# Pure_SH.net
KiCad netlist of a schematic drawn in EAGLE
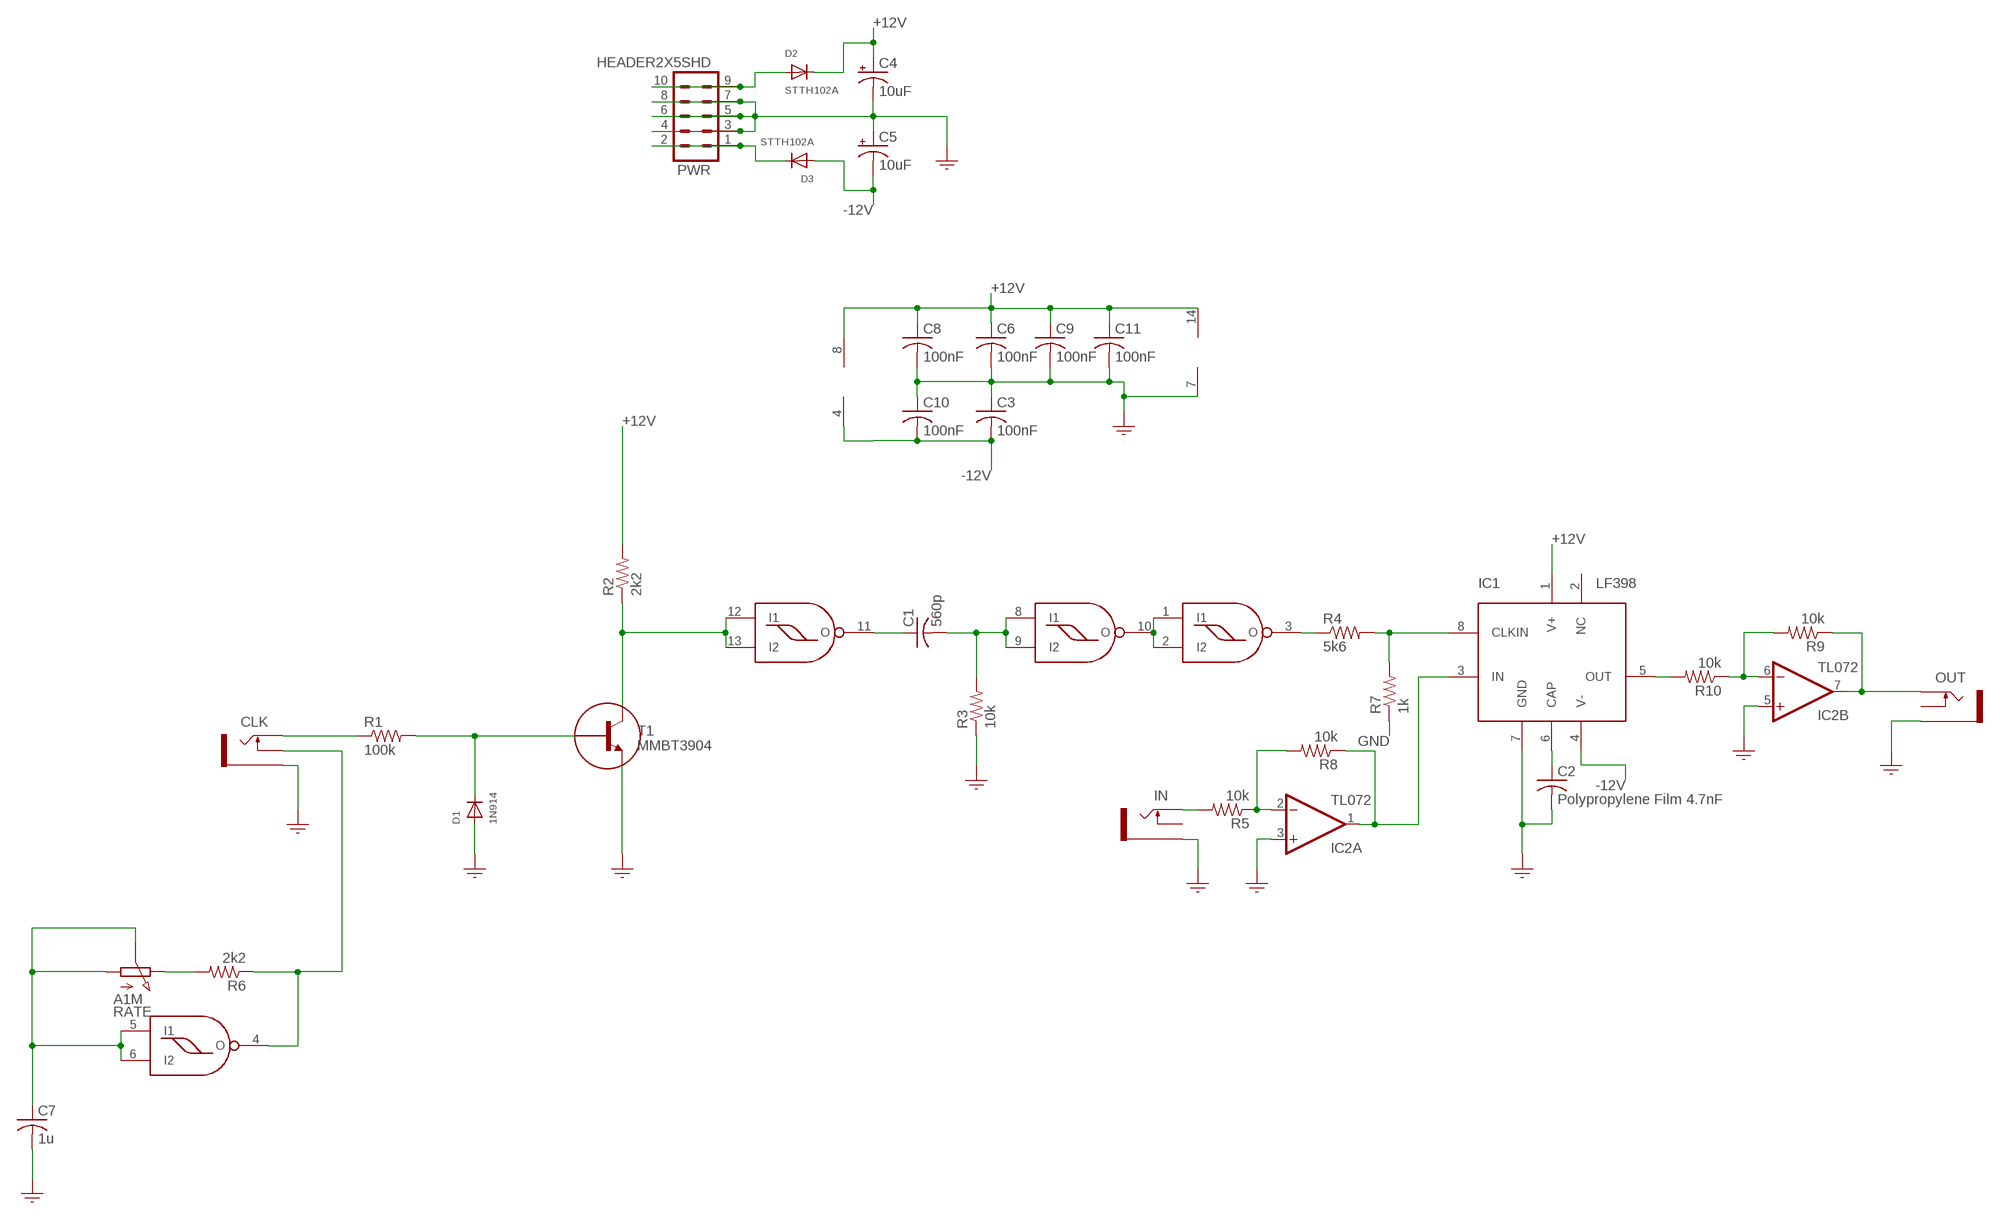
[diagram p0: schematic, sheet 1]

(export (version "E")
  (design (tool "Eeschema 10.0.6"))
  (components
    (comp (ref "C1")
      (value "560p")
      (footprint "eagle-import:C0805")
      (libsource (lib "eagle-import") (part "CAPACITOR-USC0805"))
    )
    (comp (ref "C2")
      (value "Polypropylene Film 4.7nF")
      (footprint "eagle-import:C050-045X075")
      (libsource (lib "eagle-import") (part "CAPACITOR-USC050-045X075"))
    )
    (comp (ref "C3")
      (value "100nF")
      (footprint "eagle-import:C0805")
      (libsource (lib "eagle-import") (part "CAPACITOR-USC0805"))
    )
    (comp (ref "C4")
      (value "10uF")
      (footprint "eagle-import:153CLV-0505")
      (libsource (lib "eagle-import") (part "CAPACITOR_POL-US153CLV-0505"))
    )
    (comp (ref "C5")
      (value "10uF")
      (footprint "eagle-import:153CLV-0505")
      (libsource (lib "eagle-import") (part "CAPACITOR_POL-US153CLV-0505"))
    )
    (comp (ref "C6")
      (value "100nF")
      (footprint "eagle-import:C0805")
      (libsource (lib "eagle-import") (part "CAPACITOR-USC0805"))
    )
    (comp (ref "C7")
      (value "1u")
      (footprint "eagle-import:C0805")
      (libsource (lib "eagle-import") (part "CAPACITOR-USC0805"))
    )
    (comp (ref "C8")
      (value "100nF")
      (footprint "eagle-import:C0805")
      (libsource (lib "eagle-import") (part "CAPACITOR-USC0805"))
    )
    (comp (ref "C9")
      (value "100nF")
      (footprint "eagle-import:C0805")
      (libsource (lib "eagle-import") (part "CAPACITOR-USC0805"))
    )
    (comp (ref "C10")
      (value "100nF")
      (footprint "eagle-import:C0805")
      (libsource (lib "eagle-import") (part "CAPACITOR-USC0805"))
    )
    (comp (ref "C11")
      (value "100nF")
      (footprint "eagle-import:C0805")
      (libsource (lib "eagle-import") (part "CAPACITOR-USC0805"))
    )
    (comp (ref "CLK")
      (value "PJ301M-12")
      (footprint "eagle-import:PJ301M-12")
      (libsource (lib "eagle-import") (part "SOCKET_MONO_3.5MMPJ301M-12"))
    )
    (comp (ref "D1")
      (value "1N914")
      (footprint "eagle-import:DO-41")
      (libsource (lib "eagle-import") (part "DIODEDO-41"))
    )
    (comp (ref "D2")
      (value "STTH102A")
      (footprint "eagle-import:SMADIODE")
      (libsource (lib "eagle-import") (part "DIODESMA"))
    )
    (comp (ref "D3")
      (value "STTH102A")
      (footprint "eagle-import:SMADIODE")
      (libsource (lib "eagle-import") (part "DIODESMA"))
    )
    (comp (ref "IC1")
      (value "LF398")
      (footprint "eagle-import:SOIC--8")
      (libsource (lib "eagle-import") (part "SAMPLE_HOLD_LF398"))
    )
    (comp (ref "IC2")
      (value "TL072")
      (footprint "eagle-import:SO08")
      (libsource (lib "eagle-import") (part "OPAMP_DUALD"))
    )
    (comp (ref "IC3")
      (value "cd4093")
      (footprint "eagle-import:SOIC14")
      (libsource (lib "eagle-import") (part "SCHMITT_TRIG_QUAD"))
    )
    (comp (ref "IN")
      (value "PJ301M-12")
      (footprint "eagle-import:PJ301M-12")
      (libsource (lib "eagle-import") (part "SOCKET_MONO_3.5MMPJ301M-12"))
    )
    (comp (ref "OUT")
      (value "PJ301M-12")
      (footprint "eagle-import:PJ301M-12")
      (libsource (lib "eagle-import") (part "SOCKET_MONO_3.5MMPJ301M-12"))
    )
    (comp (ref "PWR")
      (value "HEADER2X5SHD")
      (footprint "eagle-import:2X5-SHROUDED")
      (libsource (lib "eagle-import") (part "HEADER2X5SHD"))
    )
    (comp (ref "R1")
      (value "100k")
      (footprint "eagle-import:R0805")
      (libsource (lib "eagle-import") (part "RESISTOR_USR0805"))
    )
    (comp (ref "R2")
      (value "2k2")
      (footprint "eagle-import:R0805")
      (libsource (lib "eagle-import") (part "RESISTOR_USR0805"))
    )
    (comp (ref "R3")
      (value "10k")
      (footprint "eagle-import:R0805")
      (libsource (lib "eagle-import") (part "RESISTOR_USR0805"))
    )
    (comp (ref "R4")
      (value "5k6")
      (footprint "eagle-import:R0805")
      (libsource (lib "eagle-import") (part "RESISTOR_USR0805"))
    )
    (comp (ref "R5")
      (value "10k")
      (footprint "eagle-import:R0805")
      (libsource (lib "eagle-import") (part "RESISTOR_USR0805"))
    )
    (comp (ref "R6")
      (value "2k2")
      (footprint "eagle-import:R0805")
      (libsource (lib "eagle-import") (part "RESISTOR_USR0805"))
    )
    (comp (ref "R7")
      (value "1k")
      (footprint "eagle-import:R0805")
      (libsource (lib "eagle-import") (part "RESISTOR_USR0805"))
    )
    (comp (ref "R8")
      (value "10k")
      (footprint "eagle-import:R0805")
      (libsource (lib "eagle-import") (part "RESISTOR_USR0805"))
    )
    (comp (ref "R9")
      (value "10k")
      (footprint "eagle-import:R0805")
      (libsource (lib "eagle-import") (part "RESISTOR_USR0805"))
    )
    (comp (ref "R10")
      (value "10k")
      (footprint "eagle-import:R0805")
      (libsource (lib "eagle-import") (part "RESISTOR_USR0805"))
    )
    (comp (ref "RATE")
      (value "A1M")
      (footprint "eagle-import:POTENTIOMETER_9MM")
      (libsource (lib "eagle-import") (part "RESISTOR_VARIABLE9MM_POT"))
    )
    (comp (ref "T1")
      (value "MMBT3904")
      (footprint "eagle-import:SOT23")
      (libsource (lib "eagle-import") (part "TRANSISTOR_NPNSOT23"))
    )
  )
  (nets
    (net (code "1") (name "/+12V") (class "Default")
      (node (ref "C11") (pin "1") (pinfunction "1_1") (pintype "passive"))
      (node (ref "C4") (pin "+") (pinfunction "+_+") (pintype "passive"))
      (node (ref "C6") (pin "1") (pinfunction "1_1") (pintype "passive"))
      (node (ref "C8") (pin "1") (pinfunction "1_1") (pintype "passive"))
      (node (ref "C9") (pin "1") (pinfunction "1_1") (pintype "passive"))
      (node (ref "D2") (pin "C") (pinfunction "C_C") (pintype "passive"))
      (node (ref "IC1") (pin "1") (pinfunction "V+_1") (pintype "bidirectional"))
      (node (ref "IC2") (pin "8") (pinfunction "V+_8") (pintype "power_in"))
      (node (ref "IC3") (pin "14") (pinfunction "V+_14") (pintype "power_in"))
      (node (ref "R2") (pin "2") (pinfunction "2_2") (pintype "passive"))
    )
    (net (code "2") (name "/-12V") (class "Default")
      (node (ref "C10") (pin "2") (pinfunction "2_2") (pintype "passive"))
      (node (ref "C3") (pin "2") (pinfunction "2_2") (pintype "passive"))
      (node (ref "C5") (pin "-") (pinfunction "-_-") (pintype "passive"))
      (node (ref "D3") (pin "A") (pinfunction "A_A") (pintype "passive"))
      (node (ref "IC1") (pin "4") (pinfunction "V-_4") (pintype "bidirectional"))
      (node (ref "IC2") (pin "4") (pinfunction "V-_4") (pintype "power_in"))
    )
    (net (code "3") (name "GND") (class "Default")
      (node (ref "C10") (pin "1") (pinfunction "1_1") (pintype "passive"))
      (node (ref "C11") (pin "2") (pinfunction "2_2") (pintype "passive"))
      (node (ref "C2") (pin "2") (pinfunction "2_2") (pintype "passive"))
      (node (ref "C3") (pin "1") (pinfunction "1_1") (pintype "passive"))
      (node (ref "C4") (pin "-") (pinfunction "-_-") (pintype "passive"))
      (node (ref "C5") (pin "+") (pinfunction "+_+") (pintype "passive"))
      (node (ref "C6") (pin "2") (pinfunction "2_2") (pintype "passive"))
      (node (ref "C7") (pin "2") (pinfunction "2_2") (pintype "passive"))
      (node (ref "C8") (pin "2") (pinfunction "2_2") (pintype "passive"))
      (node (ref "C9") (pin "2") (pinfunction "2_2") (pintype "passive"))
      (node (ref "CLK") (pin "GND") (pinfunction "SLEEVE_GND") (pintype "passive"))
      (node (ref "D1") (pin "A") (pinfunction "A_A") (pintype "passive"))
      (node (ref "IC1") (pin "7") (pinfunction "GND_7") (pintype "bidirectional"))
      (node (ref "IC2") (pin "3") (pinfunction "+IN_3") (pintype "input"))
      (node (ref "IC2") (pin "5") (pinfunction "+IN_5") (pintype "input"))
      (node (ref "IC3") (pin "7") (pinfunction "V-_7") (pintype "power_in"))
      (node (ref "IN") (pin "GND") (pinfunction "SLEEVE_GND") (pintype "passive"))
      (node (ref "OUT") (pin "GND") (pinfunction "SLEEVE_GND") (pintype "passive"))
      (node (ref "PWR") (pin "3") (pinfunction "3_3") (pintype "passive"))
      (node (ref "PWR") (pin "4") (pinfunction "4_4") (pintype "passive"))
      (node (ref "PWR") (pin "5") (pinfunction "5_5") (pintype "passive"))
      (node (ref "PWR") (pin "6") (pinfunction "6_6") (pintype "passive"))
      (node (ref "PWR") (pin "7") (pinfunction "7_7") (pintype "passive"))
      (node (ref "PWR") (pin "8") (pinfunction "8_8") (pintype "passive"))
      (node (ref "R3") (pin "1") (pinfunction "1_1") (pintype "passive"))
      (node (ref "R7") (pin "1") (pinfunction "1_1") (pintype "passive"))
      (node (ref "T1") (pin "2") (pinfunction "E_2") (pintype "passive"))
    )
    (net (code "4") (name "Net-(CLK-PadTIP)") (class "Default")
      (node (ref "CLK") (pin "TIP") (pinfunction "TIP_TIP") (pintype "passive"))
      (node (ref "R1") (pin "1") (pinfunction "1_1") (pintype "passive"))
    )
    (net (code "5") (name "Net-(CLK-SWITCH)") (class "Default")
      (node (ref "CLK") (pin "NORM") (pinfunction "SWITCH_NORM") (pintype "passive"))
      (node (ref "IC3") (pin "4") (pinfunction "O_4") (pintype "bidirectional"))
      (node (ref "R6") (pin "1") (pinfunction "1_1") (pintype "passive"))
    )
    (net (code "6") (name "Net-(D2-PadA)") (class "Default")
      (node (ref "D2") (pin "A") (pinfunction "A_A") (pintype "passive"))
      (node (ref "PWR") (pin "10") (pinfunction "10_10") (pintype "passive"))
      (node (ref "PWR") (pin "9") (pinfunction "9_9") (pintype "passive"))
    )
    (net (code "7") (name "Net-(D3-PadC)") (class "Default")
      (node (ref "D3") (pin "C") (pinfunction "C_C") (pintype "passive"))
      (node (ref "PWR") (pin "1") (pinfunction "1_1") (pintype "passive"))
      (node (ref "PWR") (pin "2") (pinfunction "2_2") (pintype "passive"))
    )
    (net (code "8") (name "Net-(IC1-CAP)") (class "Default")
      (node (ref "C2") (pin "1") (pinfunction "1_1") (pintype "passive"))
      (node (ref "IC1") (pin "6") (pinfunction "CAP_6") (pintype "bidirectional"))
    )
    (net (code "9") (name "Net-(IC1-CLKIN)") (class "Default")
      (node (ref "IC1") (pin "8") (pinfunction "CLKIN_8") (pintype "bidirectional"))
      (node (ref "R4") (pin "2") (pinfunction "2_2") (pintype "passive"))
      (node (ref "R7") (pin "2") (pinfunction "2_2") (pintype "passive"))
    )
    (net (code "10") (name "Net-(IC1-IN)") (class "Default")
      (node (ref "IC1") (pin "3") (pinfunction "IN_3") (pintype "bidirectional"))
      (node (ref "IC2") (pin "1") (pinfunction "OUT_1") (pintype "output"))
      (node (ref "R8") (pin "1") (pinfunction "1_1") (pintype "passive"))
    )
    (net (code "11") (name "Net-(IC1-OUT)") (class "Default")
      (node (ref "IC1") (pin "5") (pinfunction "OUT_5") (pintype "bidirectional"))
      (node (ref "R10") (pin "2") (pinfunction "2_2") (pintype "passive"))
    )
    (net (code "12") (name "Net-(IC2A--IN)") (class "Default")
      (node (ref "IC2") (pin "2") (pinfunction "-IN_2") (pintype "input"))
      (node (ref "R5") (pin "1") (pinfunction "1_1") (pintype "passive"))
      (node (ref "R8") (pin "2") (pinfunction "2_2") (pintype "passive"))
    )
    (net (code "13") (name "Net-(IC2B--IN)") (class "Default")
      (node (ref "IC2") (pin "6") (pinfunction "-IN_6") (pintype "input"))
      (node (ref "R10") (pin "1") (pinfunction "1_1") (pintype "passive"))
      (node (ref "R9") (pin "2") (pinfunction "2_2") (pintype "passive"))
    )
    (net (code "14") (name "Net-(IC2B-OUT)") (class "Default")
      (node (ref "IC2") (pin "7") (pinfunction "OUT_7") (pintype "output"))
      (node (ref "OUT") (pin "TIP") (pinfunction "TIP_TIP") (pintype "passive"))
      (node (ref "R9") (pin "1") (pinfunction "1_1") (pintype "passive"))
    )
    (net (code "15") (name "Net-(IC3B-I1)") (class "Default")
      (node (ref "IC3") (pin "1") (pinfunction "I1_1") (pintype "bidirectional"))
      (node (ref "IC3") (pin "10") (pinfunction "O_10") (pintype "bidirectional"))
      (node (ref "IC3") (pin "2") (pinfunction "I2_2") (pintype "bidirectional"))
    )
    (net (code "16") (name "Net-(IC3B-O)") (class "Default")
      (node (ref "IC3") (pin "3") (pinfunction "O_3") (pintype "bidirectional"))
      (node (ref "R4") (pin "1") (pinfunction "1_1") (pintype "passive"))
    )
    (net (code "17") (name "Net-(IC3C-I1)") (class "Default")
      (node (ref "C7") (pin "1") (pinfunction "1_1") (pintype "passive"))
      (node (ref "IC3") (pin "5") (pinfunction "I1_5") (pintype "bidirectional"))
      (node (ref "IC3") (pin "6") (pinfunction "I2_6") (pintype "bidirectional"))
      (node (ref "RATE") (pin "P$1") (pinfunction "1_P$1") (pintype "passive"))
      (node (ref "RATE") (pin "P$2") (pinfunction "2_P$2") (pintype "passive"))
    )
    (net (code "18") (name "Net-(IC3D-I1)") (class "Default")
      (node (ref "C1") (pin "2") (pinfunction "2_2") (pintype "passive"))
      (node (ref "IC3") (pin "8") (pinfunction "I1_8") (pintype "bidirectional"))
      (node (ref "IC3") (pin "9") (pinfunction "I2_9") (pintype "bidirectional"))
      (node (ref "R3") (pin "2") (pinfunction "2_2") (pintype "passive"))
    )
    (net (code "19") (name "Net-(IC3E-I1)") (class "Default")
      (node (ref "IC3") (pin "12") (pinfunction "I1_12") (pintype "bidirectional"))
      (node (ref "IC3") (pin "13") (pinfunction "I2_13") (pintype "bidirectional"))
      (node (ref "R2") (pin "1") (pinfunction "1_1") (pintype "passive"))
      (node (ref "T1") (pin "3") (pinfunction "C_3") (pintype "passive"))
    )
    (net (code "20") (name "Net-(IC3E-O)") (class "Default")
      (node (ref "C1") (pin "1") (pinfunction "1_1") (pintype "passive"))
      (node (ref "IC3") (pin "11") (pinfunction "O_11") (pintype "bidirectional"))
    )
    (net (code "21") (name "Net-(IN-PadTIP)") (class "Default")
      (node (ref "IN") (pin "TIP") (pinfunction "TIP_TIP") (pintype "passive"))
      (node (ref "R5") (pin "2") (pinfunction "2_2") (pintype "passive"))
    )
    (net (code "22") (name "Net-(RATE-3)") (class "Default")
      (node (ref "R6") (pin "2") (pinfunction "2_2") (pintype "passive"))
      (node (ref "RATE") (pin "P$3") (pinfunction "3_P$3") (pintype "passive"))
    )
    (net (code "23") (name "Net-(T1-B)") (class "Default")
      (node (ref "D1") (pin "C") (pinfunction "C_C") (pintype "passive"))
      (node (ref "R1") (pin "2") (pinfunction "2_2") (pintype "passive"))
      (node (ref "T1") (pin "1") (pinfunction "B_1") (pintype "passive"))
    )
    (net (code "24") (name "unconnected-(IC1-NC-Pad2)") (class "Default")
      (node (ref "IC1") (pin "2") (pinfunction "NC_2") (pintype "bidirectional"))
    )
    (net (code "25") (name "unconnected-(IN-SWITCH-PadNORM)") (class "Default")
      (node (ref "IN") (pin "NORM") (pinfunction "SWITCH_NORM") (pintype "passive"))
    )
    (net (code "26") (name "unconnected-(OUT-SWITCH-PadNORM)") (class "Default")
      (node (ref "OUT") (pin "NORM") (pinfunction "SWITCH_NORM") (pintype "passive"))
    )
  )
)
